# RJ-45_v1_1.net
KiCad netlist of a schematic drawn in EAGLE
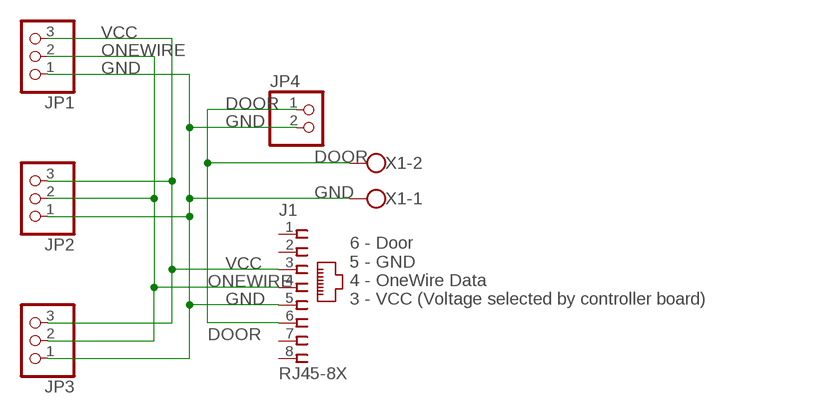
[diagram p0: schematic, sheet 1]

(export (version "E")
  (design (tool "Eeschema 10.0.6"))
  (components
    (comp (ref "J1")
      (value "RJ45-8X")
      (footprint "eagle-import:RJ45-NS-XDIM")
      (libsource (lib "eagle-import") (part "RJ45-8X"))
    )
    (comp (ref "JP1")
      (value "PINHD-1X3")
      (footprint "eagle-import:1X03")
      (libsource (lib "eagle-import") (part "PINHD-1X3"))
    )
    (comp (ref "JP2")
      (value "PINHD-1X3")
      (footprint "eagle-import:1X03")
      (libsource (lib "eagle-import") (part "PINHD-1X3"))
    )
    (comp (ref "JP3")
      (value "PINHD-1X3")
      (footprint "eagle-import:1X03")
      (libsource (lib "eagle-import") (part "PINHD-1X3"))
    )
    (comp (ref "JP4")
      (value "PINHD-1X2")
      (footprint "eagle-import:1X02")
      (libsource (lib "eagle-import") (part "PINHD-1X2"))
    )
    (comp (ref "X1")
      (value "W237-102")
      (footprint "eagle-import:W237-102")
      (fields (field (name "MPN") "237-102"))
      (libsource (lib "eagle-import") (part "W237-102"))
    )
  )
  (nets
    (net (code "1") (name "/DOOR") (class "Default")
      (node (ref "J1") (pin "6") (pinfunction "6_6") (pintype "passive"))
      (node (ref "JP4") (pin "1") (pinfunction "1_1") (pintype "passive"))
      (node (ref "X1") (pin "2") (pinfunction "KL_2") (pintype "passive"))
    )
    (net (code "2") (name "/GND") (class "Default")
      (node (ref "J1") (pin "5") (pinfunction "5_5") (pintype "passive"))
      (node (ref "JP1") (pin "1") (pinfunction "1_1") (pintype "passive"))
      (node (ref "JP2") (pin "1") (pinfunction "1_1") (pintype "passive"))
      (node (ref "JP3") (pin "1") (pinfunction "1_1") (pintype "passive"))
      (node (ref "JP4") (pin "2") (pinfunction "2_2") (pintype "passive"))
      (node (ref "X1") (pin "1") (pinfunction "KL_1") (pintype "passive"))
    )
    (net (code "3") (name "/ONEWIRE") (class "Default")
      (node (ref "J1") (pin "4") (pinfunction "4_4") (pintype "passive"))
      (node (ref "JP1") (pin "2") (pinfunction "2_2") (pintype "passive"))
      (node (ref "JP2") (pin "2") (pinfunction "2_2") (pintype "passive"))
      (node (ref "JP3") (pin "2") (pinfunction "2_2") (pintype "passive"))
    )
    (net (code "4") (name "/VCC") (class "Default")
      (node (ref "J1") (pin "3") (pinfunction "3_3") (pintype "passive"))
      (node (ref "JP1") (pin "3") (pinfunction "3_3") (pintype "passive"))
      (node (ref "JP2") (pin "3") (pinfunction "3_3") (pintype "passive"))
      (node (ref "JP3") (pin "3") (pinfunction "3_3") (pintype "passive"))
    )
    (net (code "5") (name "unconnected-(J1-Pad1)") (class "Default")
      (node (ref "J1") (pin "1") (pinfunction "1_1") (pintype "passive"))
    )
    (net (code "6") (name "unconnected-(J1-Pad2)") (class "Default")
      (node (ref "J1") (pin "2") (pinfunction "2_2") (pintype "passive"))
    )
    (net (code "7") (name "unconnected-(J1-Pad7)") (class "Default")
      (node (ref "J1") (pin "7") (pinfunction "7_7") (pintype "passive"))
    )
    (net (code "8") (name "unconnected-(J1-Pad8)") (class "Default")
      (node (ref "J1") (pin "8") (pinfunction "8_8") (pintype "passive"))
    )
  )
)
